# 1WB_DS2431_ID.net
KiCad netlist of a schematic drawn in Altium Designer
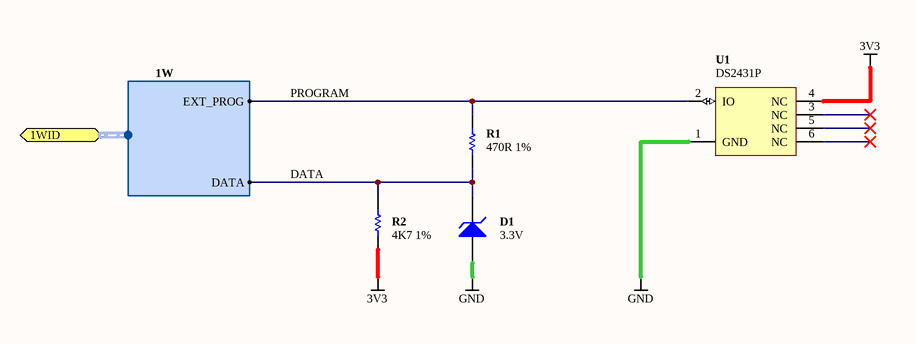
[diagram p0: 1WB_DS2431_ID.SchDoc]

(export (version "E")
  (design (tool "Eeschema 10.0.6"))
  (components
    (comp (ref "D1")
      (value "3.3V")
      (footprint "SOT95P230-3D")
      (description "Zener Diode, 3.3V")
      (libsource (lib "altium-import") (part "root_1_DIO-ZENER-1-3_"))
    )
    (comp (ref "R1")
      (value "470R 1%")
      (footprint "RESC1005-STAR")
      (description "Resistor, 470R 1% 0402 (1005)")
      (fields (field (name "TOLERANCE") "1%"))
      (libsource (lib "AltiumDesignLibrary") (part "RES"))
    )
    (comp (ref "R2")
      (value "4K7 1%")
      (footprint "RESC1005-STAR")
      (description "Resistor, 4K7 1% 0402 (1005)")
      (fields (field (name "TOLERANCE") "1%"))
      (libsource (lib "AltiumDesignLibrary") (part "RES"))
    )
    (comp (ref "U1")
      (value "DS2431P")
      (footprint "DSO-C6-D4")
      (description "EEPROM, 1-wire, 1024-bit, Surface Mount")
      (libsource (lib "AltiumDesignLibrary") (part "DS2431P"))
    )
  )
  (nets
    (net (code "2") (name "/DATA") (class "Default")
      (node (ref "D1") (pin "2") (pinfunction "K_2") (pintype "passive"))
      (node (ref "R1") (pin "2") (pinfunction "2_2") (pintype "passive"))
      (node (ref "R2") (pin "1") (pinfunction "1_1") (pintype "passive"))
    )
    (net (code "3") (name "/PROGRAM") (class "Default")
      (node (ref "R1") (pin "1") (pinfunction "1_1") (pintype "passive"))
      (node (ref "U1") (pin "2") (pinfunction "IO_2") (pintype "bidirectional"))
    )
    (net (code "5") (name "3V3") (class "Default")
      (node (ref "R2") (pin "2") (pinfunction "2_2") (pintype "passive"))
      (node (ref "U1") (pin "4") (pinfunction "NC_4") (pintype "passive"))
    )
    (net (code "6") (name "GND") (class "Default")
      (node (ref "D1") (pin "1") (pinfunction "A_1") (pintype "passive"))
      (node (ref "U1") (pin "1") (pinfunction "GND_1") (pintype "power_in"))
    )
    (net (code "7") (name "unconnected-(U1-NC-Pad3)") (class "Default")
      (node (ref "U1") (pin "3") (pinfunction "NC_3") (pintype "passive+no_connect"))
    )
    (net (code "8") (name "unconnected-(U1-NC-Pad5)") (class "Default")
      (node (ref "U1") (pin "5") (pinfunction "NC_5") (pintype "passive+no_connect"))
    )
    (net (code "9") (name "unconnected-(U1-NC-Pad6)") (class "Default")
      (node (ref "U1") (pin "6") (pinfunction "NC_6") (pintype "passive+no_connect"))
    )
  )
)
